# mainboard_mcu_v1_0.net
KiCad netlist of a schematic drawn in Altium Designer
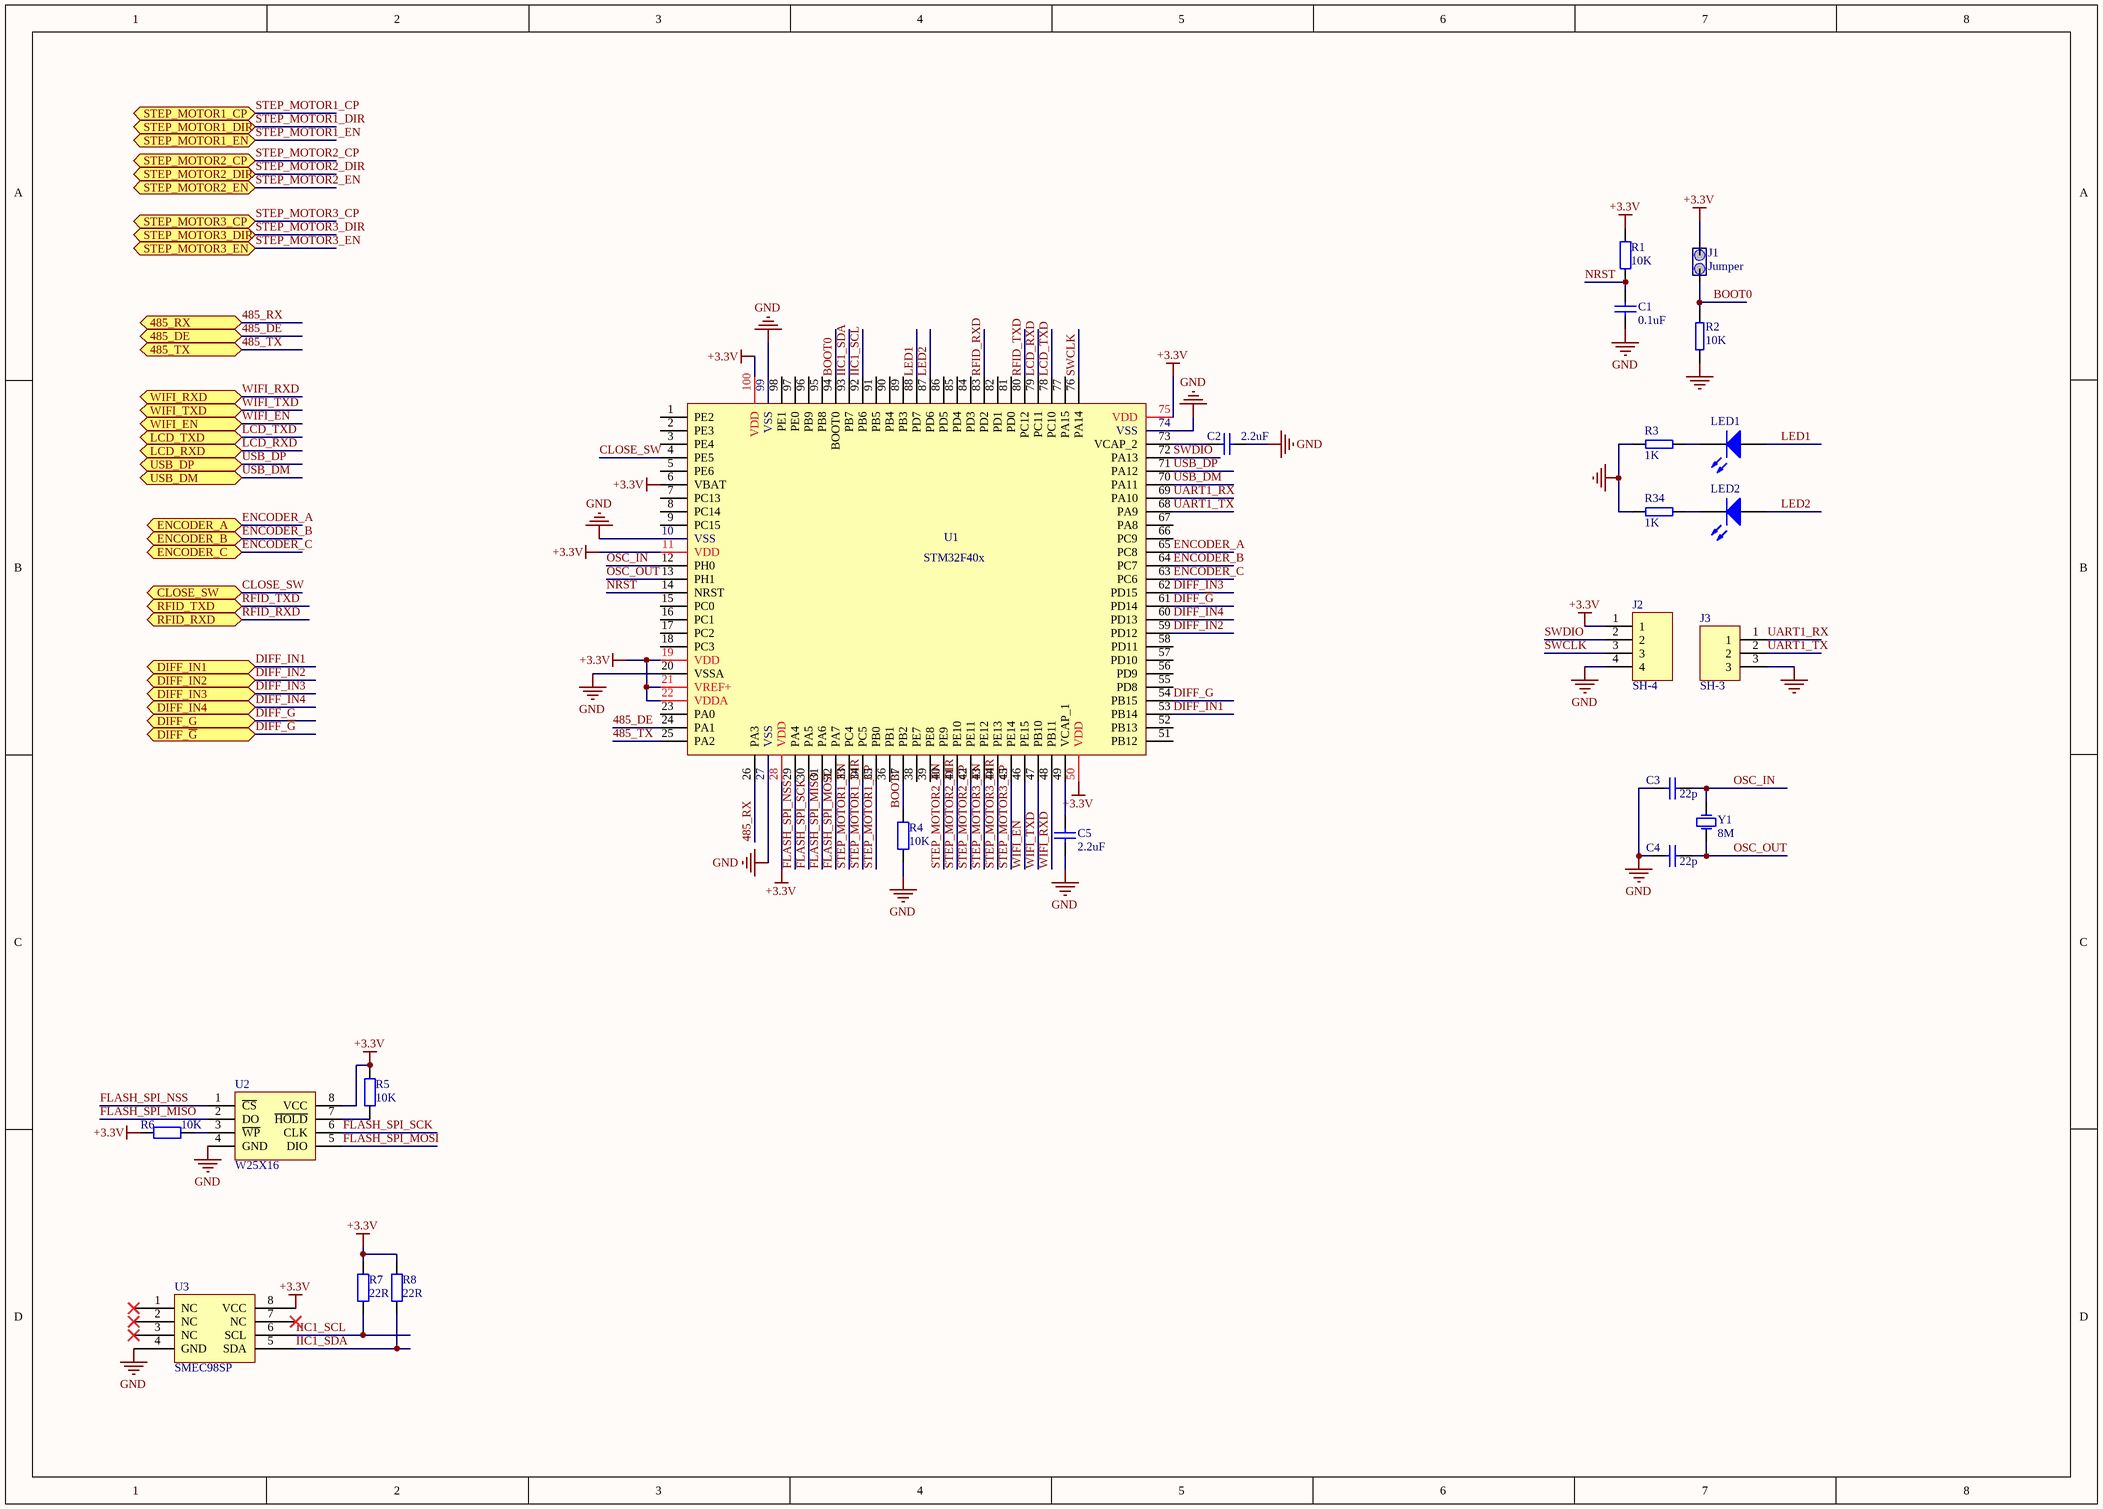
[diagram p0: mainboard_mcu.v1.0.SchDoc]

(export (version "E")
  (design (tool "Eeschema 10.0.6"))
  (components
    (comp (ref "C1")
      (value "0.1uF")
      (footprint "0805")
      (description "Capacitor")
      (fields (field (name "PUBLISHER") "Altium Limited"))
      (libsource (lib "TIAN's Schlib") (part "Cap"))
    )
    (comp (ref "C2")
      (value "2.2uF")
      (footprint "0805")
      (description "Capacitor")
      (fields (field (name "PUBLISHER") "Altium Limited"))
      (libsource (lib "TIAN's Schlib") (part "Cap"))
    )
    (comp (ref "C3")
      (value "22p")
      (footprint "0805")
      (description "Capacitor")
      (fields (field (name "PUBLISHER") "Altium Limited"))
      (libsource (lib "TIAN's Schlib") (part "Cap"))
    )
    (comp (ref "C4")
      (value "22p")
      (footprint "0805")
      (description "Capacitor")
      (fields (field (name "PUBLISHER") "Altium Limited"))
      (libsource (lib "TIAN's Schlib") (part "Cap"))
    )
    (comp (ref "C5")
      (value "2.2uF")
      (footprint "0805")
      (description "Capacitor")
      (fields (field (name "PUBLISHER") "Altium Limited"))
      (libsource (lib "TIAN's Schlib") (part "Cap"))
    )
    (comp (ref "J1") (value "Jumper") (footprint "J254-2") (libsource (lib "Connector") (part "Jumper")))
    (comp (ref "J2") (value "SH-4") (footprint "J254-4") (libsource (lib "Connector") (part "SH-4")))
    (comp (ref "J3") (value "SH-3") (footprint "J2.54-3") (libsource (lib "Connector") (part "SH-3")))
    (comp (ref "LED1")
      (value "GREEN")
      (footprint "LED")
      (description "Typical RED, GREEN, YELLOW, AMBER GaAs LED")
      (fields (field (name "PUBLISHER") "Altium Limited"))
      (libsource (lib "Miscellaneous Devices") (part "LED2"))
    )
    (comp (ref "LED2")
      (value "GREEN")
      (footprint "LED")
      (description "Typical RED, GREEN, YELLOW, AMBER GaAs LED")
      (fields (field (name "PUBLISHER") "Altium Limited"))
      (libsource (lib "Miscellaneous Devices") (part "LED2"))
    )
    (comp (ref "R1")
      (value "10K")
      (footprint "0805")
      (description "Resistor")
      (fields (field (name "PUBLISHER") "Altium Limited"))
      (libsource (lib "TIAN's Schlib") (part "Res2"))
    )
    (comp (ref "R2")
      (value "10K")
      (footprint "0805")
      (description "电阻")
      (libsource (lib "Component") (part "RES"))
    )
    (comp (ref "R3")
      (value "1K")
      (footprint "0805")
      (description "电阻")
      (libsource (lib "Component") (part "RES"))
    )
    (comp (ref "R4")
      (value "10K")
      (footprint "0805")
      (description "Resistor")
      (fields (field (name "PUBLISHER") "Altium Limited"))
      (libsource (lib "") (part "Res2_1"))
    )
    (comp (ref "R5")
      (value "10K")
      (footprint "0805")
      (description "Resistor")
      (fields (field (name "PUBLISHER") "Altium Limited"))
      (libsource (lib "") (part "Res2_1"))
    )
    (comp (ref "R6")
      (value "10K")
      (footprint "0805")
      (description "Resistor")
      (fields (field (name "PUBLISHER") "Altium Limited"))
      (libsource (lib "") (part "Res2_2"))
    )
    (comp (ref "R7")
      (value "22R")
      (footprint "0805")
      (description "Resistor")
      (fields (field (name "PUBLISHER") "Altium Limited"))
      (libsource (lib "TIAN's Schlib") (part "Res2"))
    )
    (comp (ref "R8")
      (value "22R")
      (footprint "0805")
      (description "Resistor")
      (fields (field (name "PUBLISHER") "Altium Limited"))
      (libsource (lib "TIAN's Schlib") (part "Res2"))
    )
    (comp (ref "R34")
      (value "1K")
      (footprint "0805")
      (description "电阻")
      (libsource (lib "Component") (part "RES"))
    )
    (comp (ref "U1") (value "STM32F40x") (footprint "TQFP100") (libsource (lib "Chip") (part "STM32F40x")))
    (comp (ref "U2") (value "W25X16") (footprint "SOP8") (libsource (lib "Chip") (part "W25X16")))
    (comp (ref "U3") (value "SMEC98SP") (footprint "SO-8") (libsource (lib "Chip") (part "SMEC98SP")))
    (comp (ref "Y1")
      (value "8M")
      (footprint "XTAL")
      (description "Crystal Oscillator")
      (fields (field (name "PUBLISHER") "Altium Limited"))
      (libsource (lib "TIAN's Schlib") (part "X-32.768"))
    )
  )
  (nets
    (net (code "1") (name "+3.3V") (class "Default")
      (node (ref "J1") (pin "2") (pinfunction "2_2") (pintype "passive"))
      (node (ref "J2") (pin "1") (pinfunction "1_1") (pintype "passive"))
      (node (ref "R1") (pin "2") (pinfunction "2_2") (pintype "passive"))
      (node (ref "R5") (pin "1") (pinfunction "1_1") (pintype "passive"))
      (node (ref "R6") (pin "2") (pinfunction "2_2") (pintype "passive"))
      (node (ref "R7") (pin "2") (pinfunction "2_2") (pintype "passive"))
      (node (ref "R8") (pin "2") (pinfunction "2_2") (pintype "passive"))
      (node (ref "U1") (pin "100") (pinfunction "VDD_100") (pintype "passive"))
      (node (ref "U1") (pin "11") (pinfunction "VDD_11") (pintype "passive"))
      (node (ref "U1") (pin "19") (pinfunction "VDD_19") (pintype "passive"))
      (node (ref "U1") (pin "21") (pinfunction "VREF+_21") (pintype "passive"))
      (node (ref "U1") (pin "22") (pinfunction "VDDA_22") (pintype "passive"))
      (node (ref "U1") (pin "28") (pinfunction "VDD_28") (pintype "passive"))
      (node (ref "U1") (pin "50") (pinfunction "VDD_50") (pintype "passive"))
      (node (ref "U1") (pin "6") (pinfunction "VBAT_6") (pintype "passive"))
      (node (ref "U1") (pin "75") (pinfunction "VDD_75") (pintype "passive"))
      (node (ref "U2") (pin "8") (pinfunction "VCC_8") (pintype "passive"))
      (node (ref "U3") (pin "8") (pinfunction "VCC_8") (pintype "passive"))
    )
    (net (code "2") (name "/485_DE") (class "Default")
      (node (ref "U1") (pin "24") (pinfunction "PA1_24") (pintype "passive"))
    )
    (net (code "3") (name "/485_RX") (class "Default")
      (node (ref "U1") (pin "26") (pinfunction "PA3_26") (pintype "passive"))
    )
    (net (code "4") (name "/485_TX") (class "Default")
      (node (ref "U1") (pin "25") (pinfunction "PA2_25") (pintype "passive"))
    )
    (net (code "5") (name "/BOOT0") (class "Default")
      (node (ref "J1") (pin "1") (pinfunction "1_1") (pintype "passive"))
      (node (ref "R2") (pin "1") (pinfunction "1_1") (pintype "passive"))
      (node (ref "U1") (pin "94") (pinfunction "BOOT0_94") (pintype "passive"))
    )
    (net (code "6") (name "/BOOT1") (class "Default")
      (node (ref "R4") (pin "1") (pinfunction "1_1") (pintype "passive"))
      (node (ref "U1") (pin "37") (pinfunction "PB2_37") (pintype "passive"))
    )
    (net (code "7") (name "/CLOSE_SW") (class "Default")
      (node (ref "U1") (pin "4") (pinfunction "PE5_4") (pintype "passive"))
    )
    (net (code "8") (name "/DIFF_G") (class "Default")
      (node (ref "U1") (pin "54") (pinfunction "PB15_54") (pintype "passive"))
    )
    (net (code "9") (name "/DIFF_IN1") (class "Default")
      (node (ref "U1") (pin "53") (pinfunction "PB14_53") (pintype "passive"))
    )
    (net (code "10") (name "/DIFF_IN2") (class "Default")
      (node (ref "U1") (pin "59") (pinfunction "PD12_59") (pintype "passive"))
    )
    (net (code "11") (name "/DIFF_IN3") (class "Default")
      (node (ref "U1") (pin "62") (pinfunction "PD15_62") (pintype "passive"))
    )
    (net (code "12") (name "/DIFF_IN4") (class "Default")
      (node (ref "U1") (pin "60") (pinfunction "PD13_60") (pintype "passive"))
    )
    (net (code "13") (name "/DIFF_~{G}") (class "Default")
      (node (ref "U1") (pin "61") (pinfunction "PD14_61") (pintype "passive"))
    )
    (net (code "14") (name "/ENCODER_A") (class "Default")
      (node (ref "U1") (pin "65") (pinfunction "PC8_65") (pintype "passive"))
    )
    (net (code "15") (name "/ENCODER_B") (class "Default")
      (node (ref "U1") (pin "64") (pinfunction "PC7_64") (pintype "passive"))
    )
    (net (code "16") (name "/ENCODER_C") (class "Default")
      (node (ref "U1") (pin "63") (pinfunction "PC6_63") (pintype "passive"))
    )
    (net (code "17") (name "/FLASH_SPI_MISO") (class "Default")
      (node (ref "U1") (pin "31") (pinfunction "PA6_31") (pintype "passive"))
      (node (ref "U2") (pin "2") (pinfunction "DO_2") (pintype "passive"))
    )
    (net (code "18") (name "/FLASH_SPI_MOSI") (class "Default")
      (node (ref "U1") (pin "32") (pinfunction "PA7_32") (pintype "passive"))
      (node (ref "U2") (pin "5") (pinfunction "DIO_5") (pintype "passive"))
    )
    (net (code "19") (name "/FLASH_SPI_NSS") (class "Default")
      (node (ref "U1") (pin "29") (pinfunction "PA4_29") (pintype "passive"))
      (node (ref "U2") (pin "1") (pinfunction "~{CS}_1") (pintype "passive"))
    )
    (net (code "20") (name "/FLASH_SPI_SCK") (class "Default")
      (node (ref "U1") (pin "30") (pinfunction "PA5_30") (pintype "passive"))
      (node (ref "U2") (pin "6") (pinfunction "CLK_6") (pintype "passive"))
    )
    (net (code "21") (name "/IIC1_SCL") (class "Default")
      (node (ref "R7") (pin "1") (pinfunction "1_1") (pintype "passive"))
      (node (ref "U1") (pin "92") (pinfunction "PB6_92") (pintype "passive"))
      (node (ref "U3") (pin "6") (pinfunction "SCL_6") (pintype "passive"))
    )
    (net (code "22") (name "/IIC1_SDA") (class "Default")
      (node (ref "R8") (pin "1") (pinfunction "1_1") (pintype "passive"))
      (node (ref "U1") (pin "93") (pinfunction "PB7_93") (pintype "passive"))
      (node (ref "U3") (pin "5") (pinfunction "SDA_5") (pintype "passive"))
    )
    (net (code "23") (name "/LCD_RXD") (class "Default")
      (node (ref "U1") (pin "79") (pinfunction "PC11_79") (pintype "passive"))
    )
    (net (code "24") (name "/LCD_TXD") (class "Default")
      (node (ref "U1") (pin "78") (pinfunction "PC10_78") (pintype "passive"))
    )
    (net (code "25") (name "/LED1") (class "Default")
      (node (ref "LED1") (pin "1") (pinfunction "A_1") (pintype "passive"))
      (node (ref "U1") (pin "88") (pinfunction "PD7_88") (pintype "passive"))
    )
    (net (code "26") (name "/LED2") (class "Default")
      (node (ref "LED2") (pin "1") (pinfunction "A_1") (pintype "passive"))
      (node (ref "U1") (pin "87") (pinfunction "PD6_87") (pintype "passive"))
    )
    (net (code "27") (name "/NRST") (class "Default")
      (node (ref "C1") (pin "2") (pinfunction "2_2") (pintype "passive"))
      (node (ref "R1") (pin "1") (pinfunction "1_1") (pintype "passive"))
      (node (ref "U1") (pin "14") (pinfunction "NRST_14") (pintype "passive"))
    )
    (net (code "28") (name "/OSC_IN") (class "Default")
      (node (ref "C3") (pin "1") (pinfunction "1_1") (pintype "passive"))
      (node (ref "U1") (pin "12") (pinfunction "PH0_12") (pintype "passive"))
      (node (ref "Y1") (pin "2") (pinfunction "OSC2_2") (pintype "passive"))
    )
    (net (code "29") (name "/OSC_OUT") (class "Default")
      (node (ref "C4") (pin "1") (pinfunction "1_1") (pintype "passive"))
      (node (ref "U1") (pin "13") (pinfunction "PH1_13") (pintype "passive"))
      (node (ref "Y1") (pin "1") (pinfunction "OSC1_1") (pintype "passive"))
    )
    (net (code "30") (name "/RFID_RXD") (class "Default")
      (node (ref "U1") (pin "83") (pinfunction "PD2_83") (pintype "passive"))
    )
    (net (code "31") (name "/RFID_TXD") (class "Default")
      (node (ref "U1") (pin "80") (pinfunction "PC12_80") (pintype "passive"))
    )
    (net (code "32") (name "/STEP_MOTOR1_CP") (class "Default")
      (node (ref "U1") (pin "35") (pinfunction "PB0_35") (pintype "passive"))
    )
    (net (code "33") (name "/STEP_MOTOR1_DIR") (class "Default")
      (node (ref "U1") (pin "34") (pinfunction "PC5_34") (pintype "passive"))
    )
    (net (code "34") (name "/STEP_MOTOR1_EN") (class "Default")
      (node (ref "U1") (pin "33") (pinfunction "PC4_33") (pintype "passive"))
    )
    (net (code "35") (name "/STEP_MOTOR2_CP") (class "Default")
      (node (ref "U1") (pin "42") (pinfunction "PE11_42") (pintype "passive"))
    )
    (net (code "36") (name "/STEP_MOTOR2_DIR") (class "Default")
      (node (ref "U1") (pin "41") (pinfunction "PE10_41") (pintype "passive"))
    )
    (net (code "37") (name "/STEP_MOTOR2_EN") (class "Default")
      (node (ref "U1") (pin "40") (pinfunction "PE9_40") (pintype "passive"))
    )
    (net (code "38") (name "/STEP_MOTOR3_CP") (class "Default")
      (node (ref "U1") (pin "45") (pinfunction "PE14_45") (pintype "passive"))
    )
    (net (code "39") (name "/STEP_MOTOR3_DIR") (class "Default")
      (node (ref "U1") (pin "44") (pinfunction "PE13_44") (pintype "passive"))
    )
    (net (code "40") (name "/STEP_MOTOR3_EN") (class "Default")
      (node (ref "U1") (pin "43") (pinfunction "PE12_43") (pintype "passive"))
    )
    (net (code "41") (name "/SWCLK") (class "Default")
      (node (ref "J2") (pin "3") (pinfunction "3_3") (pintype "passive"))
      (node (ref "U1") (pin "76") (pinfunction "PA14_76") (pintype "passive"))
    )
    (net (code "42") (name "/SWDIO") (class "Default")
      (node (ref "J2") (pin "2") (pinfunction "2_2") (pintype "passive"))
      (node (ref "U1") (pin "72") (pinfunction "PA13_72") (pintype "passive"))
    )
    (net (code "43") (name "/UART1_RX") (class "Default")
      (node (ref "J3") (pin "1") (pinfunction "1_1") (pintype "passive"))
      (node (ref "U1") (pin "69") (pinfunction "PA10_69") (pintype "passive"))
    )
    (net (code "44") (name "/UART1_TX") (class "Default")
      (node (ref "J3") (pin "2") (pinfunction "2_2") (pintype "passive"))
      (node (ref "U1") (pin "68") (pinfunction "PA9_68") (pintype "passive"))
    )
    (net (code "45") (name "/USB_DM") (class "Default")
      (node (ref "U1") (pin "70") (pinfunction "PA11_70") (pintype "passive"))
    )
    (net (code "46") (name "/USB_DP") (class "Default")
      (node (ref "U1") (pin "71") (pinfunction "PA12_71") (pintype "passive"))
    )
    (net (code "47") (name "/WIFI_EN") (class "Default")
      (node (ref "U1") (pin "46") (pinfunction "PE15_46") (pintype "passive"))
    )
    (net (code "48") (name "/WIFI_RXD") (class "Default")
      (node (ref "U1") (pin "48") (pinfunction "PB11_48") (pintype "passive"))
    )
    (net (code "49") (name "/WIFI_TXD") (class "Default")
      (node (ref "U1") (pin "47") (pinfunction "PB10_47") (pintype "passive"))
    )
    (net (code "50") (name "GND") (class "Default")
      (node (ref "C1") (pin "1") (pinfunction "1_1") (pintype "passive"))
      (node (ref "C2") (pin "1") (pinfunction "1_1") (pintype "passive"))
      (node (ref "C3") (pin "2") (pinfunction "2_2") (pintype "passive"))
      (node (ref "C4") (pin "2") (pinfunction "2_2") (pintype "passive"))
      (node (ref "C5") (pin "2") (pinfunction "2_2") (pintype "passive"))
      (node (ref "J2") (pin "4") (pinfunction "4_4") (pintype "passive"))
      (node (ref "J3") (pin "3") (pinfunction "3_3") (pintype "passive"))
      (node (ref "R2") (pin "2") (pinfunction "2_2") (pintype "passive"))
      (node (ref "R3") (pin "2") (pinfunction "2_2") (pintype "passive"))
      (node (ref "R34") (pin "2") (pinfunction "2_2") (pintype "passive"))
      (node (ref "R4") (pin "2") (pinfunction "2_2") (pintype "passive"))
      (node (ref "U1") (pin "10") (pinfunction "VSS_10") (pintype "passive"))
      (node (ref "U1") (pin "20") (pinfunction "VSSA_20") (pintype "passive"))
      (node (ref "U1") (pin "27") (pinfunction "VSS_27") (pintype "passive"))
      (node (ref "U1") (pin "74") (pinfunction "VSS_74") (pintype "passive"))
      (node (ref "U1") (pin "99") (pinfunction "VSS_99") (pintype "passive"))
      (node (ref "U2") (pin "4") (pinfunction "GND_4") (pintype "passive"))
      (node (ref "U3") (pin "4") (pinfunction "GND_4") (pintype "passive"))
    )
    (net (code "51") (name "Net-(LED1-K)") (class "Default")
      (node (ref "LED1") (pin "2") (pinfunction "K_2") (pintype "passive"))
      (node (ref "R3") (pin "1") (pinfunction "1_1") (pintype "passive"))
    )
    (net (code "52") (name "Net-(LED2-K)") (class "Default")
      (node (ref "LED2") (pin "2") (pinfunction "K_2") (pintype "passive"))
      (node (ref "R34") (pin "1") (pinfunction "1_1") (pintype "passive"))
    )
    (net (code "53") (name "Net-(U1-VCAP_1)") (class "Default")
      (node (ref "C5") (pin "1") (pinfunction "1_1") (pintype "passive"))
      (node (ref "U1") (pin "49") (pinfunction "VCAP_1_49") (pintype "passive"))
    )
    (net (code "54") (name "Net-(U1-VCAP_2)") (class "Default")
      (node (ref "C2") (pin "2") (pinfunction "2_2") (pintype "passive"))
      (node (ref "U1") (pin "73") (pinfunction "VCAP_2_73") (pintype "passive"))
    )
    (net (code "55") (name "Net-(U2-~{HOLD})") (class "Default")
      (node (ref "R5") (pin "2") (pinfunction "2_2") (pintype "passive"))
      (node (ref "U2") (pin "7") (pinfunction "~{HOLD}_7") (pintype "passive"))
    )
    (net (code "56") (name "Net-(U2-~{WP})") (class "Default")
      (node (ref "R6") (pin "1") (pinfunction "1_1") (pintype "passive"))
      (node (ref "U2") (pin "3") (pinfunction "~{WP}_3") (pintype "passive"))
    )
    (net (code "57") (name "unconnected-(U1-PA0-Pad23)") (class "Default")
      (node (ref "U1") (pin "23") (pinfunction "PA0_23") (pintype "passive"))
    )
    (net (code "58") (name "unconnected-(U1-PA8-Pad67)") (class "Default")
      (node (ref "U1") (pin "67") (pinfunction "PA8_67") (pintype "passive"))
    )
    (net (code "59") (name "unconnected-(U1-PA15-Pad77)") (class "Default")
      (node (ref "U1") (pin "77") (pinfunction "PA15_77") (pintype "passive"))
    )
    (net (code "60") (name "unconnected-(U1-PB1-Pad36)") (class "Default")
      (node (ref "U1") (pin "36") (pinfunction "PB1_36") (pintype "passive"))
    )
    (net (code "61") (name "unconnected-(U1-PB3-Pad89)") (class "Default")
      (node (ref "U1") (pin "89") (pinfunction "PB3_89") (pintype "passive"))
    )
    (net (code "62") (name "unconnected-(U1-PB4-Pad90)") (class "Default")
      (node (ref "U1") (pin "90") (pinfunction "PB4_90") (pintype "passive"))
    )
    (net (code "63") (name "unconnected-(U1-PB5-Pad91)") (class "Default")
      (node (ref "U1") (pin "91") (pinfunction "PB5_91") (pintype "passive"))
    )
    (net (code "64") (name "unconnected-(U1-PB8-Pad95)") (class "Default")
      (node (ref "U1") (pin "95") (pinfunction "PB8_95") (pintype "passive"))
    )
    (net (code "65") (name "unconnected-(U1-PB9-Pad96)") (class "Default")
      (node (ref "U1") (pin "96") (pinfunction "PB9_96") (pintype "passive"))
    )
    (net (code "66") (name "unconnected-(U1-PB12-Pad51)") (class "Default")
      (node (ref "U1") (pin "51") (pinfunction "PB12_51") (pintype "passive"))
    )
    (net (code "67") (name "unconnected-(U1-PB13-Pad52)") (class "Default")
      (node (ref "U1") (pin "52") (pinfunction "PB13_52") (pintype "passive"))
    )
    (net (code "68") (name "unconnected-(U1-PC0-Pad15)") (class "Default")
      (node (ref "U1") (pin "15") (pinfunction "PC0_15") (pintype "passive"))
    )
    (net (code "69") (name "unconnected-(U1-PC1-Pad16)") (class "Default")
      (node (ref "U1") (pin "16") (pinfunction "PC1_16") (pintype "passive"))
    )
    (net (code "70") (name "unconnected-(U1-PC2-Pad17)") (class "Default")
      (node (ref "U1") (pin "17") (pinfunction "PC2_17") (pintype "passive"))
    )
    (net (code "71") (name "unconnected-(U1-PC3-Pad18)") (class "Default")
      (node (ref "U1") (pin "18") (pinfunction "PC3_18") (pintype "passive"))
    )
    (net (code "72") (name "unconnected-(U1-PC9-Pad66)") (class "Default")
      (node (ref "U1") (pin "66") (pinfunction "PC9_66") (pintype "passive"))
    )
    (net (code "73") (name "unconnected-(U1-PC13-Pad7)") (class "Default")
      (node (ref "U1") (pin "7") (pinfunction "PC13_7") (pintype "passive"))
    )
    (net (code "74") (name "unconnected-(U1-PC14-Pad8)") (class "Default")
      (node (ref "U1") (pin "8") (pinfunction "PC14_8") (pintype "passive"))
    )
    (net (code "75") (name "unconnected-(U1-PC15-Pad9)") (class "Default")
      (node (ref "U1") (pin "9") (pinfunction "PC15_9") (pintype "passive"))
    )
    (net (code "76") (name "unconnected-(U1-PD0-Pad81)") (class "Default")
      (node (ref "U1") (pin "81") (pinfunction "PD0_81") (pintype "passive"))
    )
    (net (code "77") (name "unconnected-(U1-PD1-Pad82)") (class "Default")
      (node (ref "U1") (pin "82") (pinfunction "PD1_82") (pintype "passive"))
    )
    (net (code "78") (name "unconnected-(U1-PD3-Pad84)") (class "Default")
      (node (ref "U1") (pin "84") (pinfunction "PD3_84") (pintype "passive"))
    )
    (net (code "79") (name "unconnected-(U1-PD4-Pad85)") (class "Default")
      (node (ref "U1") (pin "85") (pinfunction "PD4_85") (pintype "passive"))
    )
    (net (code "80") (name "unconnected-(U1-PD5-Pad86)") (class "Default")
      (node (ref "U1") (pin "86") (pinfunction "PD5_86") (pintype "passive"))
    )
    (net (code "81") (name "unconnected-(U1-PD8-Pad55)") (class "Default")
      (node (ref "U1") (pin "55") (pinfunction "PD8_55") (pintype "passive"))
    )
    (net (code "82") (name "unconnected-(U1-PD9-Pad56)") (class "Default")
      (node (ref "U1") (pin "56") (pinfunction "PD9_56") (pintype "passive"))
    )
    (net (code "83") (name "unconnected-(U1-PD10-Pad57)") (class "Default")
      (node (ref "U1") (pin "57") (pinfunction "PD10_57") (pintype "passive"))
    )
    (net (code "84") (name "unconnected-(U1-PD11-Pad58)") (class "Default")
      (node (ref "U1") (pin "58") (pinfunction "PD11_58") (pintype "passive"))
    )
    (net (code "85") (name "unconnected-(U1-PE0-Pad97)") (class "Default")
      (node (ref "U1") (pin "97") (pinfunction "PE0_97") (pintype "passive"))
    )
    (net (code "86") (name "unconnected-(U1-PE1-Pad98)") (class "Default")
      (node (ref "U1") (pin "98") (pinfunction "PE1_98") (pintype "passive"))
    )
    (net (code "87") (name "unconnected-(U1-PE2-Pad1)") (class "Default")
      (node (ref "U1") (pin "1") (pinfunction "PE2_1") (pintype "passive"))
    )
    (net (code "88") (name "unconnected-(U1-PE3-Pad2)") (class "Default")
      (node (ref "U1") (pin "2") (pinfunction "PE3_2") (pintype "passive"))
    )
    (net (code "89") (name "unconnected-(U1-PE4-Pad3)") (class "Default")
      (node (ref "U1") (pin "3") (pinfunction "PE4_3") (pintype "passive"))
    )
    (net (code "90") (name "unconnected-(U1-PE6-Pad5)") (class "Default")
      (node (ref "U1") (pin "5") (pinfunction "PE6_5") (pintype "passive"))
    )
    (net (code "91") (name "unconnected-(U1-PE7-Pad38)") (class "Default")
      (node (ref "U1") (pin "38") (pinfunction "PE7_38") (pintype "passive"))
    )
    (net (code "92") (name "unconnected-(U1-PE8-Pad39)") (class "Default")
      (node (ref "U1") (pin "39") (pinfunction "PE8_39") (pintype "passive"))
    )
    (net (code "93") (name "unconnected-(U3-NC-Pad1)") (class "Default")
      (node (ref "U3") (pin "1") (pinfunction "NC_1") (pintype "passive+no_connect"))
    )
    (net (code "94") (name "unconnected-(U3-NC-Pad2)") (class "Default")
      (node (ref "U3") (pin "2") (pinfunction "NC_2") (pintype "passive+no_connect"))
    )
    (net (code "95") (name "unconnected-(U3-NC-Pad3)") (class "Default")
      (node (ref "U3") (pin "3") (pinfunction "NC_3") (pintype "passive+no_connect"))
    )
    (net (code "96") (name "unconnected-(U3-NC-Pad7)") (class "Default")
      (node (ref "U3") (pin "7") (pinfunction "NC_7") (pintype "passive+no_connect"))
    )
  )
)
